# LcsNodes-Dual-Block-Controller-B_02_10.net
KiCad netlist of a schematic drawn in EasyEDA
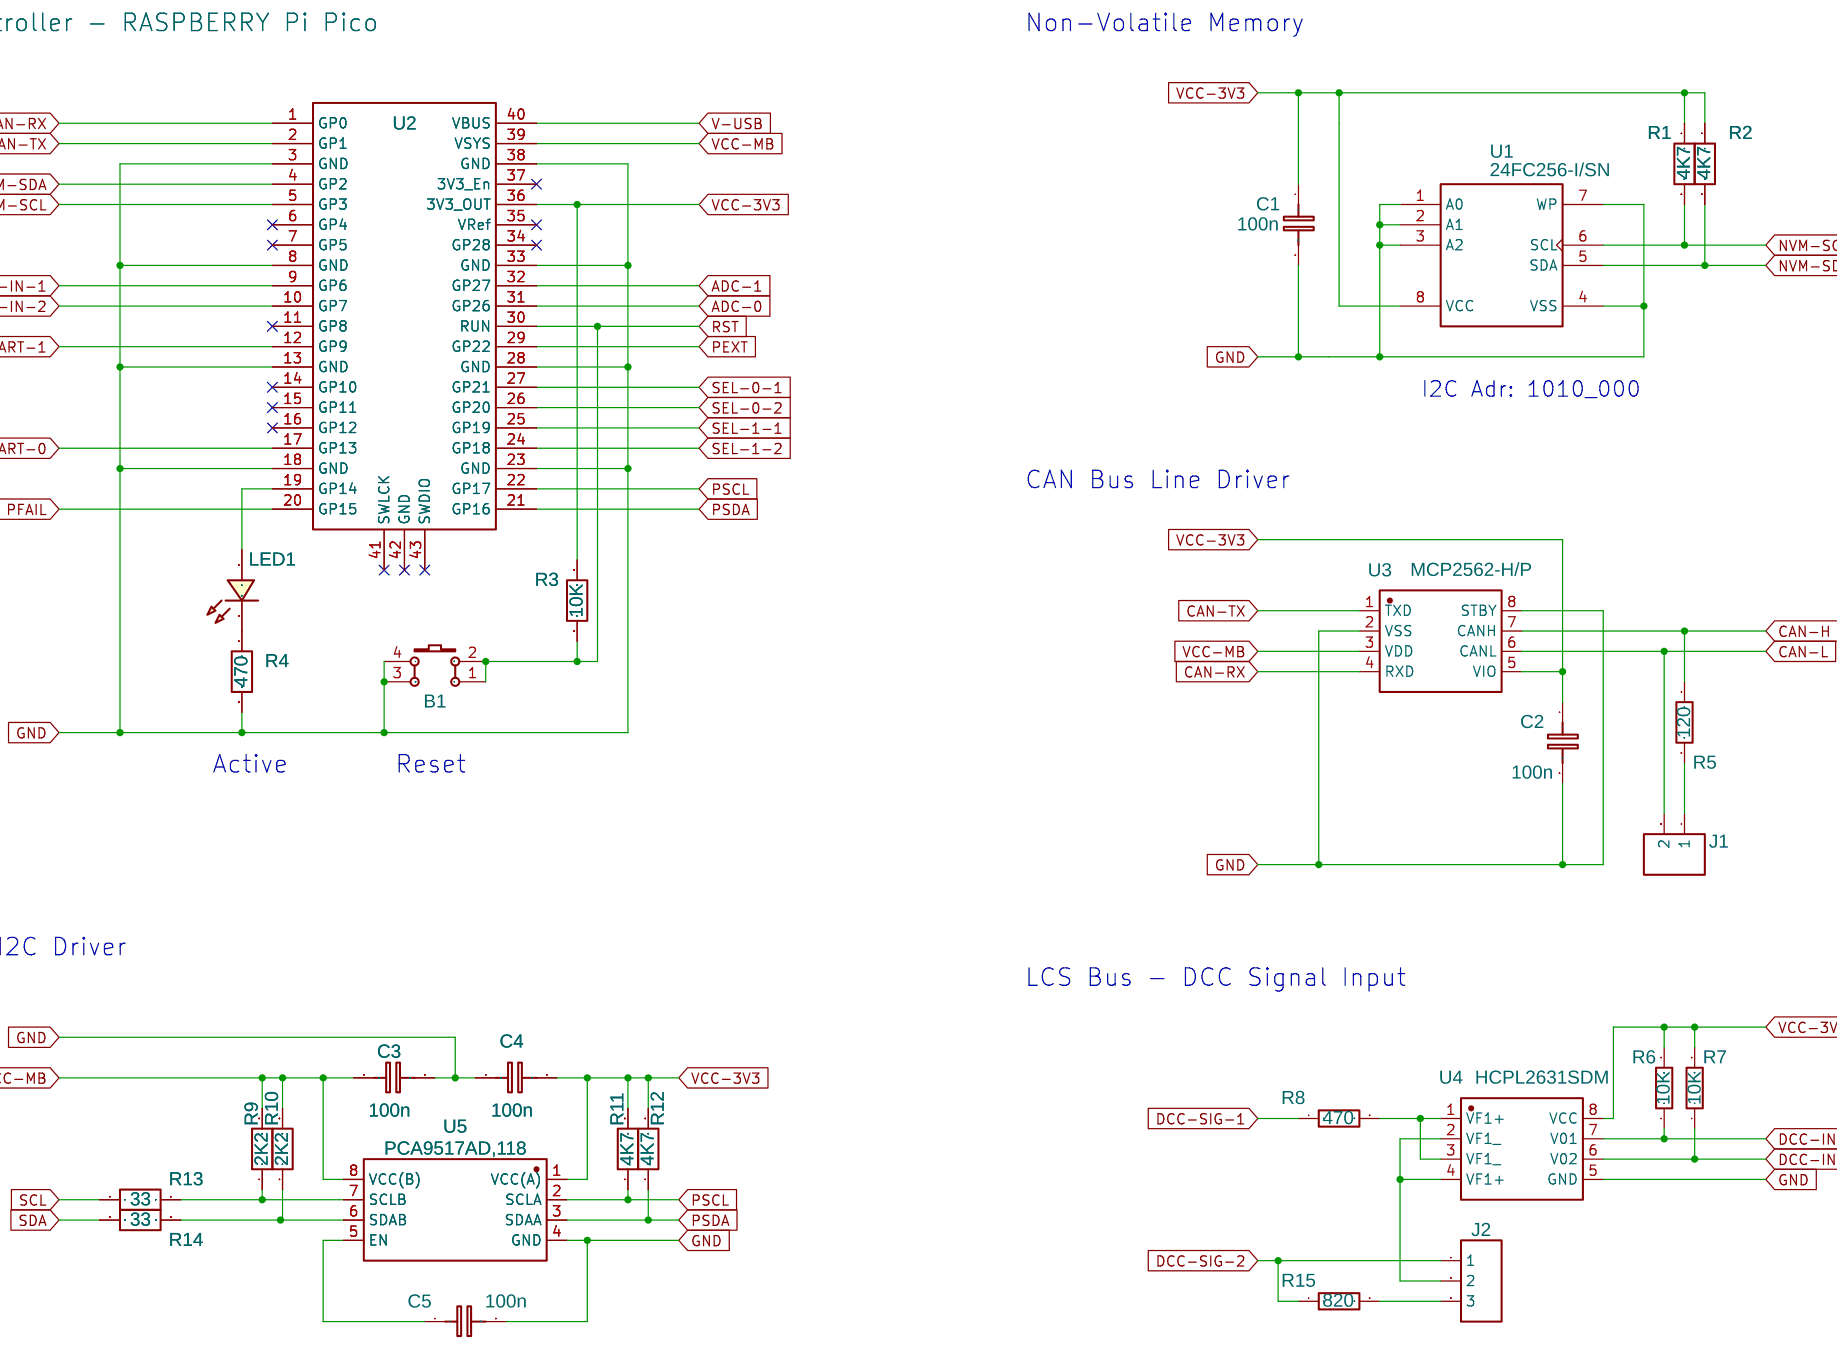
[diagram p0: Main Controller]
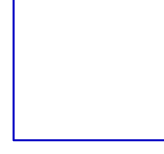
[diagram p1: High Level Schematic]
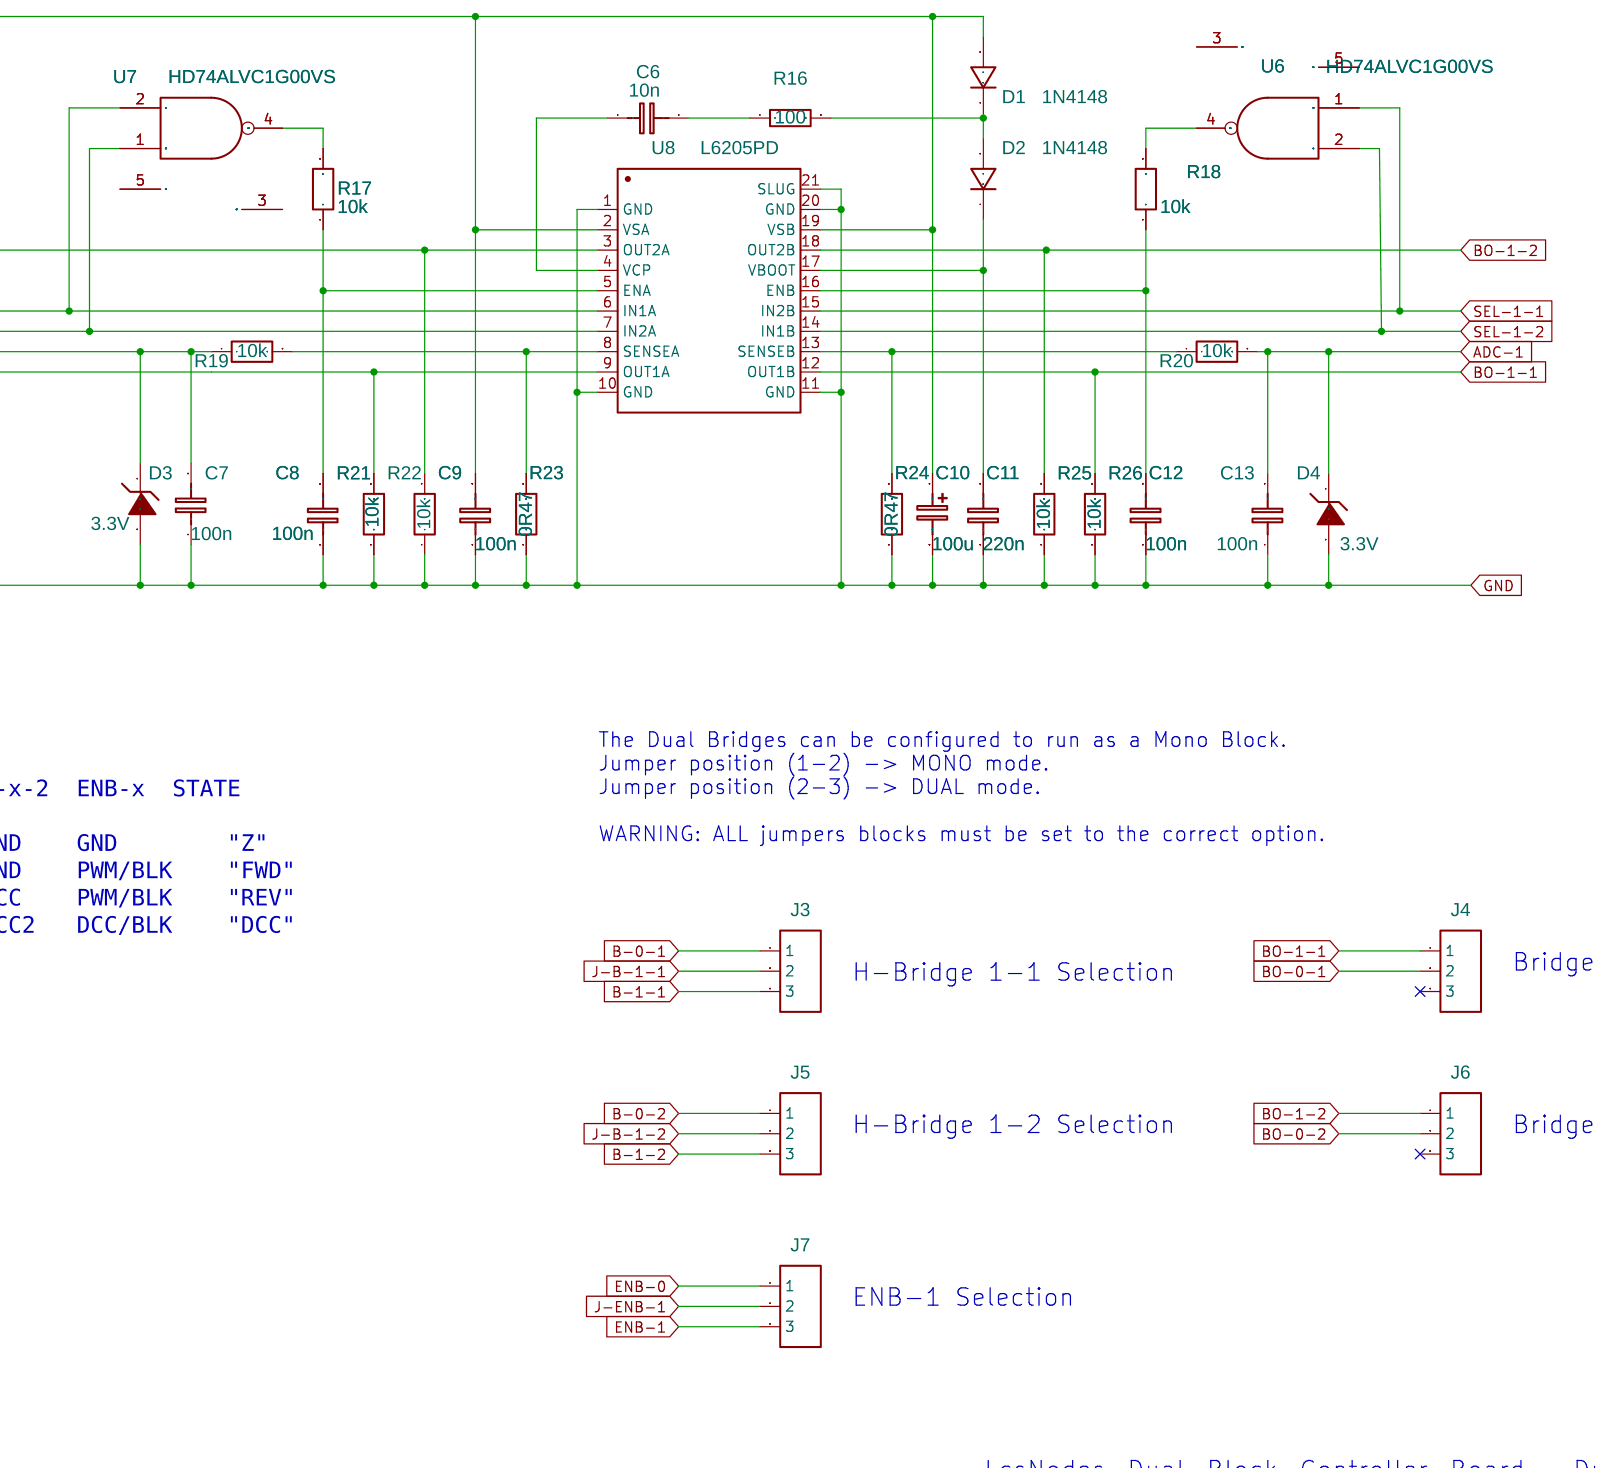
[diagram p2: Dual Power Unit]
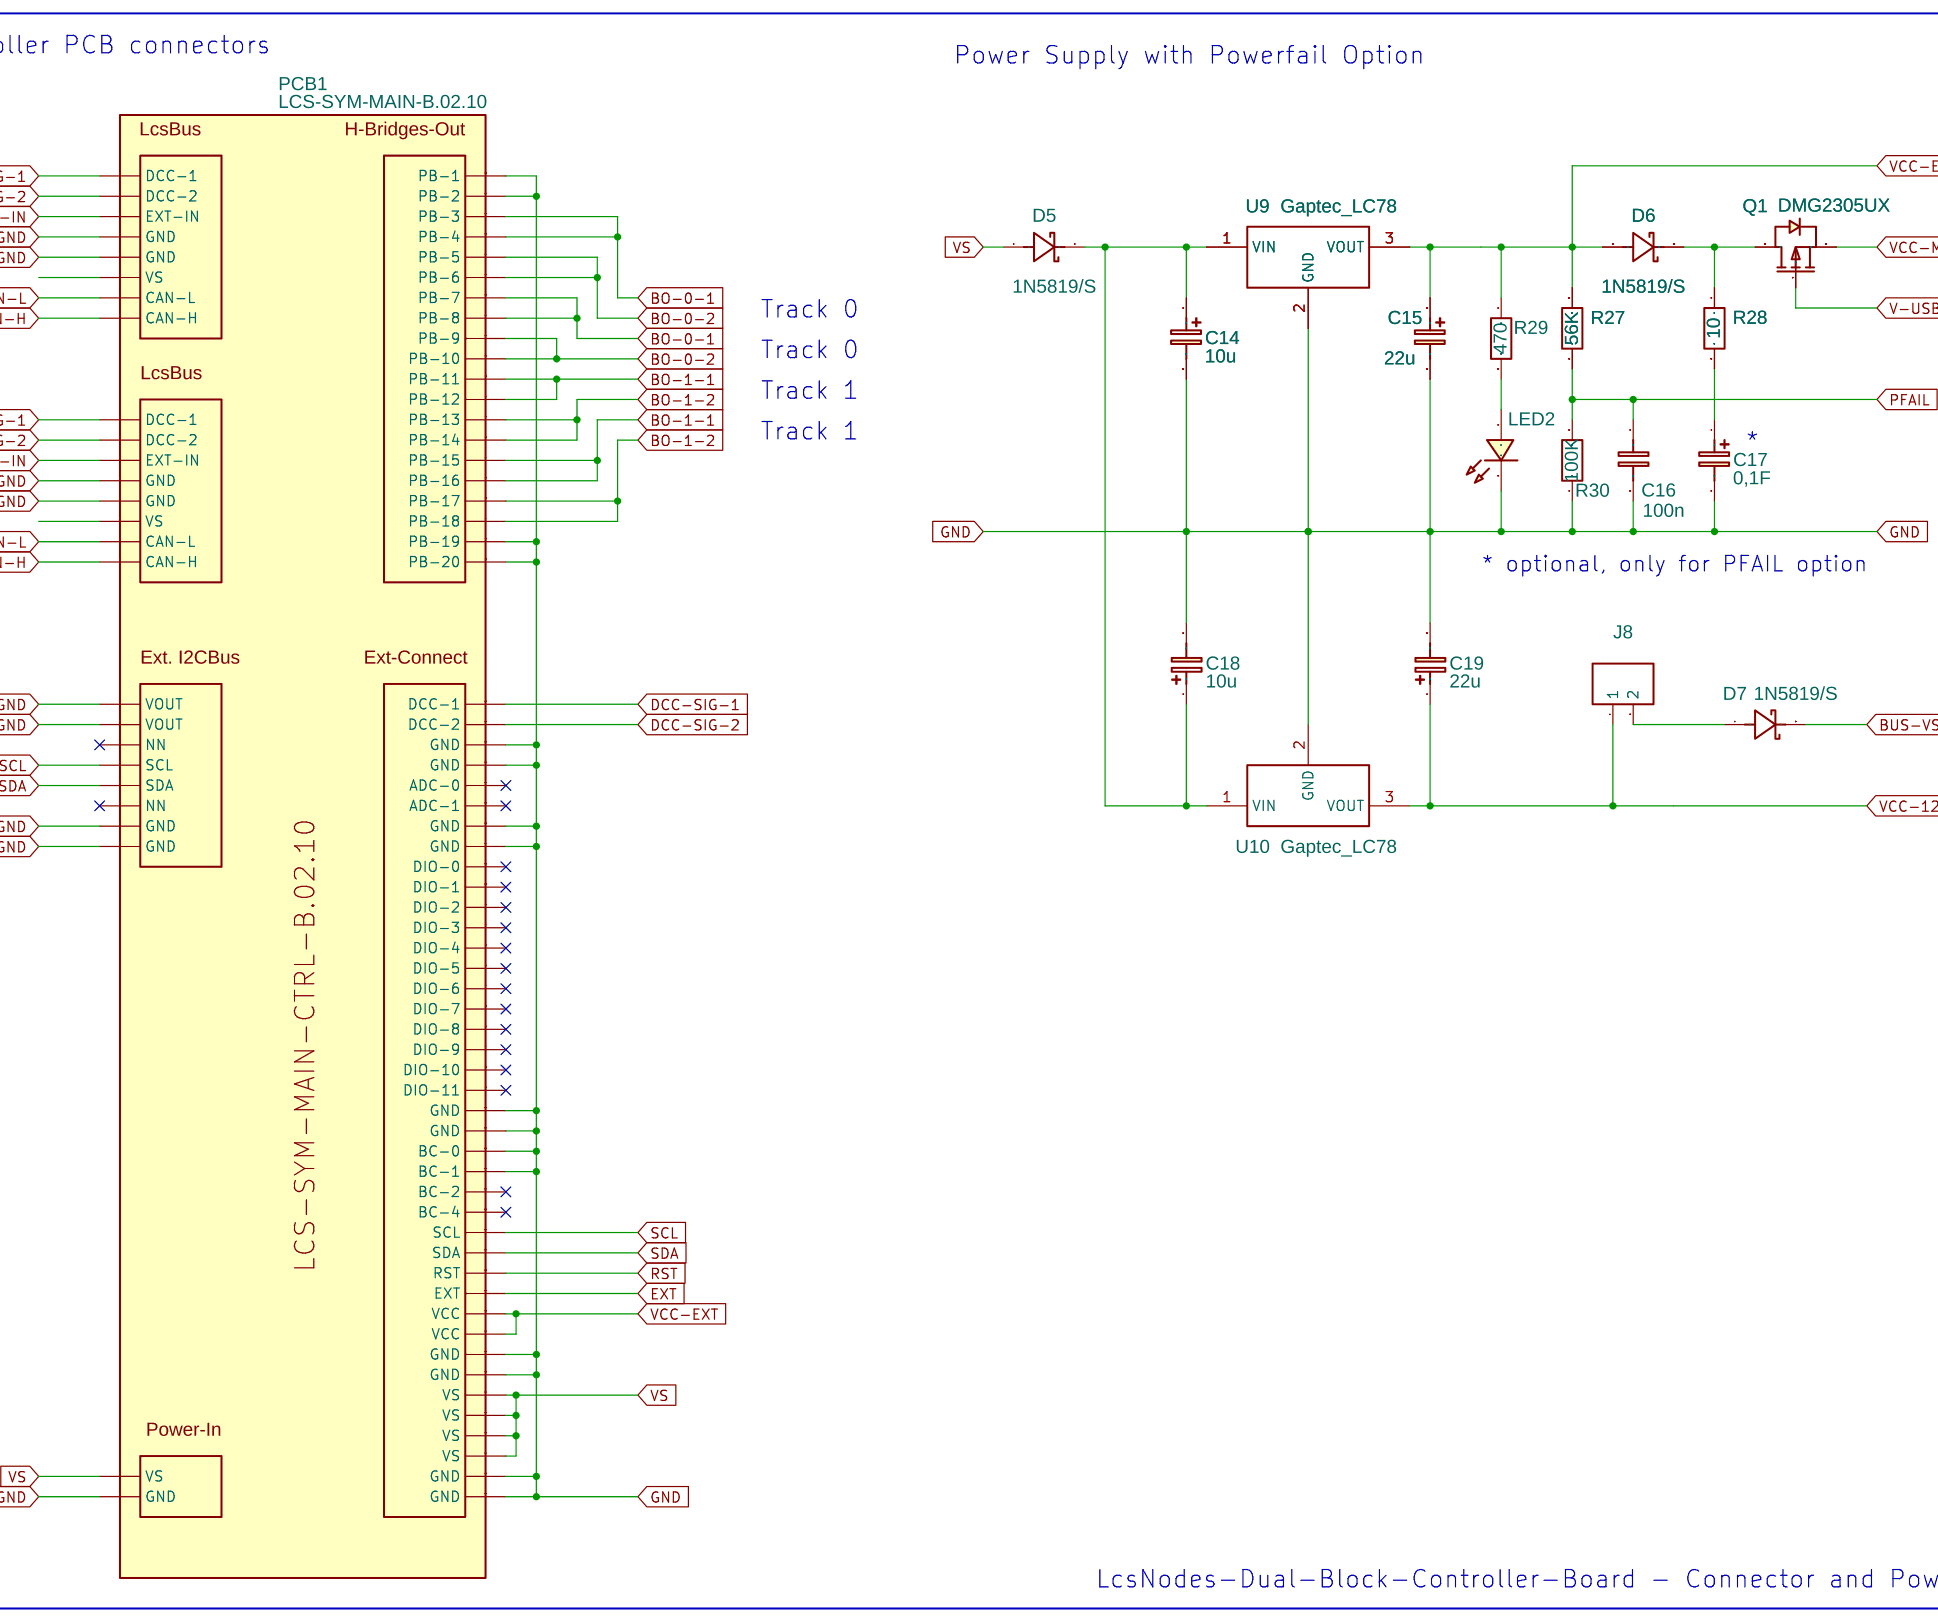
[diagram p3: Power Supply, Connectors]

(export (version "E")
  (design (tool "Eeschema 10.0.6"))
  (components
    (comp (ref "B1")
      (value "Opt")
      (fields (field (name "Manufacturer Part") "K2-1102DP-E4SW-04") (field (name "Manufacturer") "韩国韩荣"))
      (libsource (lib "") (part "K4-6×6_TH"))
    )
    (comp (ref "C1") (value "100n") (libsource (lib "") (part "C_0603_EU_1")))
    (comp (ref "C2") (value "100n") (libsource (lib "") (part "C_0603_EU")))
    (comp (ref "C3") (value "100n") (libsource (lib "") (part "C_RAD-0.2_EU")))
    (comp (ref "C4") (value "100n") (libsource (lib "") (part "C_RAD-0.2_EU")))
    (comp (ref "C5") (value "100n") (libsource (lib "") (part "C_RAD-0.2_EU")))
    (comp (ref "J1") (value "HDR-M-2.54_1x2") (libsource (lib "") (part "HDR-M-2.54_1x2")))
    (comp (ref "J2") (value "HDR-M-2.54_1x3") (libsource (lib "") (part "HDR-M-2.54_1x3")))
    (comp (ref "LED1")
      (value "LED-0805_G")
      (fields (field (name "Manufacturer Part") "NCD0805G1") (field (name "Manufacturer") "国星光电"))
      (libsource (lib "") (part "LED-0805_G"))
    )
    (comp (ref "R1") (value "4K7") (libsource (lib "") (part "R_0805_EU_1")))
    (comp (ref "R2") (value "4K7") (libsource (lib "") (part "R_0805_EU_1")))
    (comp (ref "R3") (value "10K") (libsource (lib "") (part "R_0805_EU")))
    (comp (ref "R4") (value "470") (libsource (lib "") (part "R_0805_EU_1")))
    (comp (ref "R5") (value "120") (libsource (lib "") (part "RESISTOR-AXIAL-0.1")))
    (comp (ref "R6")
      (value "10K")
      (fields (field (name "Manufacturer Part") "SR1206JR-7W4K7L") (field (name "Manufacturer") "YAGEO(国巨)"))
      (libsource (lib "") (part "SR1206JR-7W4K7L"))
    )
    (comp (ref "R7")
      (value "10K")
      (fields (field (name "Manufacturer Part") "SR1206JR-7W4K7L") (field (name "Manufacturer") "YAGEO(国巨)"))
      (libsource (lib "") (part "SR1206JR-7W4K7L"))
    )
    (comp (ref "R8")
      (value "470")
      (fields (field (name "Manufacturer Part") "SR1206JR-7W4K7L") (field (name "Manufacturer") "YAGEO(国巨)"))
      (libsource (lib "") (part "SR1206JR-7W4K7L_1"))
    )
    (comp (ref "R9") (value "2K2") (libsource (lib "") (part "R_0805_EU")))
    (comp (ref "R10") (value "2K2") (libsource (lib "") (part "R_0805_EU")))
    (comp (ref "R11") (value "4K7") (libsource (lib "") (part "R_0805_EU")))
    (comp (ref "R12") (value "4K7") (libsource (lib "") (part "R_0805_EU")))
    (comp (ref "R13") (value "33") (libsource (lib "") (part "R_1206_EU")))
    (comp (ref "R14") (value "33") (libsource (lib "") (part "R_1206_EU")))
    (comp (ref "R15")
      (value "820")
      (fields (field (name "Manufacturer Part") "SR1206JR-7W4K7L") (field (name "Manufacturer") "YAGEO(国巨)"))
      (libsource (lib "") (part "SR1206JR-7W4K7L_1"))
    )
    (comp (ref "U1")
      (value "24FC256-I/SN")
      (fields (field (name "Manufacturer") "MICROCHIP(美国微芯)"))
      (libsource (lib "") (part "24FC256-I/SN"))
    )
    (comp (ref "U2")
      (value "Main Controller - RASPBERRY Pi Pico")
      (libsource (lib "") (part "RASPBERRY Pi Pico Through Holes"))
    )
    (comp (ref "U3")
      (value "MCP2562-H/P")
      (fields (field (name "Manufacturer") "MICROCHIP(美国微芯)"))
      (libsource (lib "") (part "MCP2562-H/P"))
    )
    (comp (ref "U4")
      (value "HCPL2631SDM")
      (fields (field (name "Manufacturer") "onsemi(安森美)"))
      (libsource (lib "") (part "HCPL2631SDM"))
    )
    (comp (ref "U5")
      (value "PCA9517AD,118")
      (fields (field (name "Manufacturer") "NXP(恩智浦)"))
      (libsource (lib "") (part "PCA9517AD,118"))
    )
    (comp (ref "C6") (value "10n") (libsource (lib "") (part "C_0603_EU_2")))
    (comp (ref "C7") (value "100n") (libsource (lib "") (part "C_0603_EU")))
    (comp (ref "C8") (value "100n") (libsource (lib "") (part "C_0603_EU")))
    (comp (ref "C9") (value "100n") (libsource (lib "") (part "C_0603_EU_1")))
    (comp (ref "C10") (value "100u") (libsource (lib "") (part "CE_SMD_D5.0×H5.5_EU")))
    (comp (ref "C11") (value "220n") (libsource (lib "") (part "C_0603_EU_1")))
    (comp (ref "C12") (value "100n") (libsource (lib "") (part "C_0603_EU_1")))
    (comp (ref "C13") (value "100n") (libsource (lib "") (part "C_0603_EU_1")))
    (comp (ref "D1")
      (value "1N4148")
      (fields (field (name "Manufacturer") "SEMTECH"))
      (libsource (lib "") (part "1N4148"))
    )
    (comp (ref "D2")
      (value "1N4148")
      (fields (field (name "Manufacturer") "SEMTECH"))
      (libsource (lib "") (part "1N4148"))
    )
    (comp (ref "D3")
      (value "3.3V")
      (fields (field (name "Manufacturer Part") "Diode Zener") (field (name "Manufacturer") "SEMTECH"))
      (libsource (lib "") (part "Diode Zener"))
    )
    (comp (ref "D4")
      (value "3.3V")
      (fields (field (name "Manufacturer Part") "Diode Zener") (field (name "Manufacturer") "SEMTECH"))
      (libsource (lib "") (part "Diode Zener"))
    )
    (comp (ref "J3") (value "HDR-M-2.54_1x3") (libsource (lib "") (part "HDR-M-2.54_1x3")))
    (comp (ref "J4") (value "HDR-M-2.54_1x3") (libsource (lib "") (part "HDR-M-2.54_1x3")))
    (comp (ref "J5") (value "HDR-M-2.54_1x3") (libsource (lib "") (part "HDR-M-2.54_1x3")))
    (comp (ref "J6") (value "HDR-M-2.54_1x3") (libsource (lib "") (part "HDR-M-2.54_1x3")))
    (comp (ref "J7") (value "HDR-M-2.54_1x3") (libsource (lib "") (part "HDR-M-2.54_1x3")))
    (comp (ref "R16") (value "100") (libsource (lib "") (part "RESISTOR-AXIAL-0.1")))
    (comp (ref "R17") (value "10k") (libsource (lib "") (part "R_AXIAL-0.3_EU")))
    (comp (ref "R18") (value "10k") (libsource (lib "") (part "R_AXIAL-0.3_EU")))
    (comp (ref "R19") (value "10k") (libsource (lib "") (part "R_AXIAL-0.3_EU_1")))
    (comp (ref "R20") (value "10k") (libsource (lib "") (part "R_AXIAL-0.3_EU_1")))
    (comp (ref "R21") (value "10k") (libsource (lib "") (part "R_AXIAL-0.3_EU")))
    (comp (ref "R22") (value "10k") (libsource (lib "") (part "R_AXIAL-0.3_EU")))
    (comp (ref "R23") (value "0R47") (libsource (lib "") (part "R_AXIAL-0.5_EU")))
    (comp (ref "R24") (value "0R47") (libsource (lib "") (part "R_AXIAL-0.5_EU")))
    (comp (ref "R25") (value "10k") (libsource (lib "") (part "R_AXIAL-0.3_EU")))
    (comp (ref "R26") (value "10k") (libsource (lib "") (part "R_AXIAL-0.3_EU")))
    (comp (ref "U6") (value "HD74ALVC1G00VS") (libsource (lib "") (part "HD74ALVC1G00VS_1")))
    (comp (ref "U7") (value "HD74ALVC1G00VS") (libsource (lib "") (part "HD74ALVC1G00VS")))
    (comp (ref "U8")
      (value "L6205PD")
      (fields (field (name "Manufacturer Part") "L6205PD013TR") (field (name "Manufacturer") "ST(意法半导体)"))
      (libsource (lib "") (part "L6205PD"))
    )
    (comp (ref "C14") (value "10u") (libsource (lib "") (part "CE_SMD_D5.0×H5.5_EU")))
    (comp (ref "C15") (value "22u") (libsource (lib "") (part "CE_SMD_D5.0×H5.5_EU")))
    (comp (ref "C16") (value "100n") (libsource (lib "") (part "C_RAD-0.2_EU")))
    (comp (ref "C17") (value "0,1F") (libsource (lib "") (part "C_Tan_SMD_A_EU")))
    (comp (ref "C18") (value "10u") (libsource (lib "") (part "CE_SMD_D5.0×H5.5_EU_1")))
    (comp (ref "C19") (value "22u") (libsource (lib "") (part "CE_SMD_D5.0×H5.5_EU_1")))
    (comp (ref "D5") (value "1N5819/S") (libsource (lib "") (part "1N5819/S")))
    (comp (ref "D6") (value "1N5819/S") (libsource (lib "") (part "1N5819/S")))
    (comp (ref "D7") (value "1N5819/S") (libsource (lib "") (part "1N5819/S")))
    (comp (ref "J8") (value "HDR-M-2.54_1x2") (libsource (lib "") (part "HDR-M-2.54_1x2")))
    (comp (ref "LED2")
      (value "LED-0805_G")
      (fields (field (name "Manufacturer Part") "NCD0805G1") (field (name "Manufacturer") "国星光电"))
      (libsource (lib "") (part "LED-0805_G"))
    )
    (comp (ref "PCB1") (value "LCS-SYM-MAIN-B.02.10") (libsource (lib "") (part "LCS-SYM-MAIN-B.02.10")))
    (comp (ref "Q1")
      (value "DMG2305UX")
      (fields (field (name "Manufacturer") "TECH PUBLIC(台舟)"))
      (libsource (lib "") (part "DMG2305UX"))
    )
    (comp (ref "R27") (value "56K") (libsource (lib "") (part "R_AXIAL-0.3_EU")))
    (comp (ref "R28") (value "10") (libsource (lib "") (part "R_AXIAL-0.3_EU_1")))
    (comp (ref "R29") (value "470") (libsource (lib "") (part "R_0805_EU")))
    (comp (ref "R30") (value "100K") (libsource (lib "") (part "R_AXIAL-0.3_EU")))
    (comp (ref "U9") (value "Gaptec_LC78") (libsource (lib "") (part "Gaptec_LC78_1")))
    (comp (ref "U10") (value "Gaptec_LC78") (libsource (lib "") (part "Gaptec_LC78")))
  )
  (nets
    (net (code "1") (name "ADC-0") (class "Default")
      (node (ref "C7") (pin "2") (pinfunction "2_2") (pintype "unspecified"))
      (node (ref "D3") (pin "1") (pinfunction "C_1") (pintype "unspecified"))
      (node (ref "R19") (pin "1") (pinfunction "1_1") (pintype "unspecified"))
      (node (ref "U2") (pin "31") (pinfunction "GP26_31") (pintype "unspecified"))
    )
    (net (code "2") (name "ADC-1") (class "Default")
      (node (ref "C13") (pin "2") (pinfunction "2_2") (pintype "unspecified"))
      (node (ref "D4") (pin "1") (pinfunction "C_1") (pintype "unspecified"))
      (node (ref "R20") (pin "2") (pinfunction "2_2") (pintype "unspecified"))
      (node (ref "U2") (pin "32") (pinfunction "GP27_32") (pintype "unspecified"))
    )
    (net (code "3") (name "B-0-1") (class "Default")
      (node (ref "J3") (pin "1") (pinfunction "1_1") (pintype "input"))
    )
    (net (code "4") (name "B-0-2") (class "Default")
      (node (ref "J5") (pin "1") (pinfunction "1_1") (pintype "input"))
    )
    (net (code "5") (name "B-1-1") (class "Default")
      (node (ref "J3") (pin "3") (pinfunction "3_3") (pintype "input"))
    )
    (net (code "6") (name "B-1-2") (class "Default")
      (node (ref "J5") (pin "3") (pinfunction "3_3") (pintype "input"))
    )
    (net (code "7") (name "BO-0-1") (class "Default")
      (node (ref "J4") (pin "2") (pinfunction "2_2") (pintype "input"))
      (node (ref "PCB1") (pin "32") (pinfunction "PB-3_32") (pintype "unspecified"))
      (node (ref "PCB1") (pin "33") (pinfunction "PB-4_33") (pintype "unspecified"))
      (node (ref "PCB1") (pin "36") (pinfunction "PB-7_36") (pintype "unspecified"))
      (node (ref "PCB1") (pin "37") (pinfunction "PB-8_37") (pintype "unspecified"))
      (node (ref "R21") (pin "2") (pinfunction "2_2") (pintype "unspecified"))
      (node (ref "U8") (pin "9") (pinfunction "OUT1A_9") (pintype "unspecified"))
    )
    (net (code "8") (name "BO-0-2") (class "Default")
      (node (ref "J6") (pin "2") (pinfunction "2_2") (pintype "input"))
      (node (ref "PCB1") (pin "34") (pinfunction "PB-5_34") (pintype "unspecified"))
      (node (ref "PCB1") (pin "35") (pinfunction "PB-6_35") (pintype "unspecified"))
      (node (ref "PCB1") (pin "38") (pinfunction "PB-9_38") (pintype "unspecified"))
      (node (ref "PCB1") (pin "39") (pinfunction "PB-10_39") (pintype "unspecified"))
      (node (ref "R22") (pin "2") (pinfunction "2_2") (pintype "unspecified"))
      (node (ref "U8") (pin "3") (pinfunction "OUT2A_3") (pintype "unspecified"))
    )
    (net (code "9") (name "BO-1-1") (class "Default")
      (node (ref "J4") (pin "1") (pinfunction "1_1") (pintype "input"))
      (node (ref "PCB1") (pin "40") (pinfunction "PB-11_40") (pintype "unspecified"))
      (node (ref "PCB1") (pin "41") (pinfunction "PB-12_41") (pintype "unspecified"))
      (node (ref "PCB1") (pin "44") (pinfunction "PB-15_44") (pintype "unspecified"))
      (node (ref "PCB1") (pin "45") (pinfunction "PB-16_45") (pintype "unspecified"))
      (node (ref "R26") (pin "2") (pinfunction "2_2") (pintype "unspecified"))
      (node (ref "U8") (pin "12") (pinfunction "OUT1B_12") (pintype "unspecified"))
    )
    (net (code "10") (name "BO-1-2") (class "Default")
      (node (ref "J6") (pin "1") (pinfunction "1_1") (pintype "input"))
      (node (ref "PCB1") (pin "42") (pinfunction "PB-13_42") (pintype "unspecified"))
      (node (ref "PCB1") (pin "43") (pinfunction "PB-14_43") (pintype "unspecified"))
      (node (ref "PCB1") (pin "46") (pinfunction "PB-17_46") (pintype "unspecified"))
      (node (ref "PCB1") (pin "47") (pinfunction "PB-18_47") (pintype "unspecified"))
      (node (ref "R25") (pin "2") (pinfunction "2_2") (pintype "unspecified"))
      (node (ref "U8") (pin "18") (pinfunction "OUT2B_18") (pintype "unspecified"))
    )
    (net (code "11") (name "BUS-VS") (class "Default")
      (node (ref "D7") (pin "2") (pinfunction "K_2") (pintype "unspecified"))
    )
    (net (code "12") (name "CAN-H") (class "Default")
      (node (ref "PCB1") (pin "18") (pinfunction "CAN-H_18") (pintype "unspecified"))
      (node (ref "PCB1") (pin "8") (pinfunction "CAN-H_8") (pintype "unspecified"))
      (node (ref "R5") (pin "1") (pinfunction "1_1") (pintype "input"))
      (node (ref "U3") (pin "7") (pinfunction "CANH_7") (pintype "unspecified"))
    )
    (net (code "13") (name "CAN-L") (class "Default")
      (node (ref "J1") (pin "2") (pinfunction "2_2") (pintype "unspecified"))
      (node (ref "PCB1") (pin "17") (pinfunction "CAN-L_17") (pintype "unspecified"))
      (node (ref "PCB1") (pin "7") (pinfunction "CAN-L_7") (pintype "unspecified"))
      (node (ref "U3") (pin "6") (pinfunction "CANL_6") (pintype "unspecified"))
    )
    (net (code "14") (name "CAN-RX") (class "Default")
      (node (ref "U2") (pin "1") (pinfunction "GP0_1") (pintype "unspecified"))
      (node (ref "U3") (pin "4") (pinfunction "RXD_4") (pintype "unspecified"))
    )
    (net (code "15") (name "CAN-TX") (class "Default")
      (node (ref "U2") (pin "2") (pinfunction "GP1_2") (pintype "unspecified"))
      (node (ref "U3") (pin "1") (pinfunction "TXD_1") (pintype "unspecified"))
    )
    (net (code "16") (name "DCC-IN-1") (class "Default")
      (node (ref "R6") (pin "1") (pinfunction "1_1") (pintype "unspecified"))
      (node (ref "U2") (pin "9") (pinfunction "GP6_9") (pintype "unspecified"))
      (node (ref "U4") (pin "7") (pinfunction "V01_7") (pintype "unspecified"))
    )
    (net (code "17") (name "DCC-IN-2") (class "Default")
      (node (ref "R7") (pin "1") (pinfunction "1_1") (pintype "unspecified"))
      (node (ref "U2") (pin "10") (pinfunction "GP7_10") (pintype "unspecified"))
      (node (ref "U4") (pin "6") (pinfunction "V02_6") (pintype "unspecified"))
    )
    (net (code "18") (name "DCC-SIG-1") (class "Default")
      (node (ref "PCB1") (pin "1") (pinfunction "DCC-1_1") (pintype "unspecified"))
      (node (ref "PCB1") (pin "11") (pinfunction "DCC-1_11") (pintype "unspecified"))
      (node (ref "PCB1") (pin "60") (pinfunction "DCC-1_60") (pintype "unspecified"))
      (node (ref "R8") (pin "1") (pinfunction "1_1") (pintype "unspecified"))
    )
    (net (code "19") (name "DCC-SIG-2") (class "Default")
      (node (ref "J2") (pin "1") (pinfunction "1_1") (pintype "input"))
      (node (ref "PCB1") (pin "12") (pinfunction "DCC-2_12") (pintype "unspecified"))
      (node (ref "PCB1") (pin "2") (pinfunction "DCC-2_2") (pintype "unspecified"))
      (node (ref "PCB1") (pin "61") (pinfunction "DCC-2_61") (pintype "unspecified"))
      (node (ref "R15") (pin "1") (pinfunction "1_1") (pintype "unspecified"))
    )
    (net (code "20") (name "ENB-0") (class "Default")
      (node (ref "J7") (pin "1") (pinfunction "1_1") (pintype "input"))
    )
    (net (code "21") (name "ENB-1") (class "Default")
      (node (ref "J7") (pin "3") (pinfunction "3_3") (pintype "input"))
    )
    (net (code "22") (name "EXT") (class "Default")
      (node (ref "PCB1") (pin "89") (pinfunction "EXT_89") (pintype "unspecified"))
    )
    (net (code "23") (name "EXT-IN") (class "Default")
      (node (ref "PCB1") (pin "13") (pinfunction "EXT-IN_13") (pintype "unspecified"))
      (node (ref "PCB1") (pin "3") (pinfunction "EXT-IN_3") (pintype "unspecified"))
    )
    (net (code "24") (name "GND") (class "Default")
      (node (ref "B1") (pin "3") (pinfunction "3_3") (pintype "unspecified"))
      (node (ref "B1") (pin "4") (pinfunction "4_4") (pintype "unspecified"))
      (node (ref "C1") (pin "2") (pinfunction "2_2") (pintype "unspecified"))
      (node (ref "C10") (pin "2") (pinfunction "2_2") (pintype "unspecified"))
      (node (ref "C11") (pin "1") (pinfunction "1_1") (pintype "unspecified"))
      (node (ref "C12") (pin "1") (pinfunction "1_1") (pintype "unspecified"))
      (node (ref "C13") (pin "1") (pinfunction "1_1") (pintype "unspecified"))
      (node (ref "C14") (pin "2") (pinfunction "2_2") (pintype "unspecified"))
      (node (ref "C15") (pin "2") (pinfunction "2_2") (pintype "unspecified"))
      (node (ref "C16") (pin "2") (pinfunction "2_2") (pintype "unspecified"))
      (node (ref "C17") (pin "2") (pinfunction "2_2") (pintype "unspecified"))
      (node (ref "C18") (pin "2") (pinfunction "2_2") (pintype "unspecified"))
      (node (ref "C19") (pin "2") (pinfunction "2_2") (pintype "unspecified"))
      (node (ref "C2") (pin "2") (pinfunction "2_2") (pintype "unspecified"))
      (node (ref "C3") (pin "2") (pinfunction "2_2") (pintype "unspecified"))
      (node (ref "C4") (pin "1") (pinfunction "1_1") (pintype "unspecified"))
      (node (ref "C5") (pin "2") (pinfunction "2_2") (pintype "unspecified"))
      (node (ref "C7") (pin "1") (pinfunction "1_1") (pintype "unspecified"))
      (node (ref "C8") (pin "1") (pinfunction "1_1") (pintype "unspecified"))
      (node (ref "C9") (pin "1") (pinfunction "1_1") (pintype "unspecified"))
      (node (ref "D3") (pin "2") (pinfunction "A_2") (pintype "unspecified"))
      (node (ref "D4") (pin "2") (pinfunction "A_2") (pintype "unspecified"))
      (node (ref "LED2") (pin "2") (pinfunction "2_2") (pintype "unspecified"))
      (node (ref "PCB1") (pin "101") (pinfunction "GND_101") (pintype "unspecified"))
      (node (ref "PCB1") (pin "14") (pinfunction "GND_14") (pintype "unspecified"))
      (node (ref "PCB1") (pin "15") (pinfunction "GND_15") (pintype "unspecified"))
      (node (ref "PCB1") (pin "21") (pinfunction "VOUT_21") (pintype "unspecified"))
      (node (ref "PCB1") (pin "22") (pinfunction "VOUT_22") (pintype "unspecified"))
      (node (ref "PCB1") (pin "27") (pinfunction "GND_27") (pintype "unspecified"))
      (node (ref "PCB1") (pin "28") (pinfunction "GND_28") (pintype "unspecified"))
      (node (ref "PCB1") (pin "30") (pinfunction "PB-1_30") (pintype "unspecified"))
      (node (ref "PCB1") (pin "31") (pinfunction "PB-2_31") (pintype "unspecified"))
      (node (ref "PCB1") (pin "4") (pinfunction "GND_4") (pintype "unspecified"))
      (node (ref "PCB1") (pin "48") (pinfunction "PB-19_48") (pintype "unspecified"))
      (node (ref "PCB1") (pin "49") (pinfunction "PB-20_49") (pintype "unspecified"))
      (node (ref "PCB1") (pin "5") (pinfunction "GND_5") (pintype "unspecified"))
      (node (ref "PCB1") (pin "62") (pinfunction "GND_62") (pintype "unspecified"))
      (node (ref "PCB1") (pin "63") (pinfunction "GND_63") (pintype "unspecified"))
      (node (ref "PCB1") (pin "66") (pinfunction "GND_66") (pintype "unspecified"))
      (node (ref "PCB1") (pin "67") (pinfunction "GND_67") (pintype "unspecified"))
      (node (ref "PCB1") (pin "80") (pinfunction "GND_80") (pintype "unspecified"))
      (node (ref "PCB1") (pin "81") (pinfunction "GND_81") (pintype "unspecified"))
      (node (ref "PCB1") (pin "82") (pinfunction "BC-0_82") (pintype "unspecified"))
      (node (ref "PCB1") (pin "83") (pinfunction "BC-1_83") (pintype "unspecified"))
      (node (ref "PCB1") (pin "92") (pinfunction "GND_92") (pintype "unspecified"))
      (node (ref "PCB1") (pin "93") (pinfunction "GND_93") (pintype "unspecified"))
      (node (ref "PCB1") (pin "98") (pinfunction "GND_98") (pintype "unspecified"))
      (node (ref "PCB1") (pin "99") (pinfunction "GND_99") (pintype "unspecified"))
      (node (ref "R21") (pin "1") (pinfunction "1_1") (pintype "unspecified"))
      (node (ref "R22") (pin "1") (pinfunction "1_1") (pintype "unspecified"))
      (node (ref "R23") (pin "1") (pinfunction "1_1") (pintype "unspecified"))
      (node (ref "R24") (pin "1") (pinfunction "1_1") (pintype "unspecified"))
      (node (ref "R25") (pin "1") (pinfunction "1_1") (pintype "unspecified"))
      (node (ref "R26") (pin "1") (pinfunction "1_1") (pintype "unspecified"))
      (node (ref "R30") (pin "1") (pinfunction "1_1") (pintype "unspecified"))
      (node (ref "R4") (pin "2") (pinfunction "2_2") (pintype "unspecified"))
      (node (ref "U1") (pin "1") (pinfunction "A0_1") (pintype "unspecified"))
      (node (ref "U1") (pin "2") (pinfunction "A1_2") (pintype "unspecified"))
      (node (ref "U1") (pin "3") (pinfunction "A2_3") (pintype "unspecified"))
      (node (ref "U1") (pin "4") (pinfunction "VSS_4") (pintype "passive"))
      (node (ref "U1") (pin "7") (pinfunction "WP_7") (pintype "unspecified"))
      (node (ref "U10") (pin "2") (pinfunction "GND_2") (pintype "unspecified"))
      (node (ref "U2") (pin "13") (pinfunction "GND_13") (pintype "unspecified"))
      (node (ref "U2") (pin "18") (pinfunction "GND_18") (pintype "unspecified"))
      (node (ref "U2") (pin "23") (pinfunction "GND_23") (pintype "unspecified"))
      (node (ref "U2") (pin "28") (pinfunction "GND_28") (pintype "unspecified"))
      (node (ref "U2") (pin "3") (pinfunction "GND_3") (pintype "unspecified"))
      (node (ref "U2") (pin "33") (pinfunction "GND_33") (pintype "unspecified"))
      (node (ref "U2") (pin "38") (pinfunction "GND_38") (pintype "unspecified"))
      (node (ref "U2") (pin "8") (pinfunction "GND_8") (pintype "unspecified"))
      (node (ref "U3") (pin "2") (pinfunction "VSS_2") (pintype "unspecified"))
      (node (ref "U3") (pin "8") (pinfunction "STBY_8") (pintype "unspecified"))
      (node (ref "U4") (pin "5") (pinfunction "GND_5") (pintype "unspecified"))
      (node (ref "U5") (pin "4") (pinfunction "GND_4") (pintype "unspecified"))
      (node (ref "U8") (pin "1") (pinfunction "GND_1") (pintype "unspecified"))
      (node (ref "U8") (pin "10") (pinfunction "GND_10") (pintype "unspecified"))
      (node (ref "U8") (pin "11") (pinfunction "GND_11") (pintype "unspecified"))
      (node (ref "U8") (pin "20") (pinfunction "GND_20") (pintype "unspecified"))
      (node (ref "U8") (pin "21") (pinfunction "SLUG_21") (pintype "unspecified"))
      (node (ref "U9") (pin "2") (pinfunction "GND_2") (pintype "unspecified"))
    )
    (net (code "25") (name "J-B-1-1") (class "Default")
      (node (ref "J3") (pin "2") (pinfunction "2_2") (pintype "input"))
    )
    (net (code "26") (name "J-B-1-2") (class "Default")
      (node (ref "J5") (pin "2") (pinfunction "2_2") (pintype "input"))
    )
    (net (code "27") (name "J-ENB-1") (class "Default")
      (node (ref "J7") (pin "2") (pinfunction "2_2") (pintype "input"))
    )
    (net (code "28") (name "NVM-SCL") (class "Default")
      (node (ref "R1") (pin "2") (pinfunction "2_2") (pintype "unspecified"))
      (node (ref "U1") (pin "6") (pinfunction "SCL_6") (pintype "unspecified"))
      (node (ref "U2") (pin "5") (pinfunction "GP3_5") (pintype "unspecified"))
    )
    (net (code "29") (name "NVM-SDA") (class "Default")
      (node (ref "R2") (pin "2") (pinfunction "2_2") (pintype "unspecified"))
      (node (ref "U1") (pin "5") (pinfunction "SDA_5") (pintype "bidirectional"))
      (node (ref "U2") (pin "4") (pinfunction "GP2_4") (pintype "unspecified"))
    )
    (net (code "30") (name "Net-(C6-Pad2)") (class "Default")
      (node (ref "C6") (pin "2") (pinfunction "2_2") (pintype "unspecified"))
      (node (ref "R16") (pin "1") (pinfunction "1_1") (pintype "input"))
    )
    (net (code "31") (name "Net-(C17-Pad1)") (class "Default")
      (node (ref "C17") (pin "1") (pinfunction "1_1") (pintype "unspecified"))
      (node (ref "R28") (pin "2") (pinfunction "2_2") (pintype "unspecified"))
    )
    (net (code "32") (name "Net-(D1-2)") (class "Default")
      (node (ref "D1") (pin "1") (pinfunction "2_1") (pintype "unspecified"))
      (node (ref "D2") (pin "2") (pinfunction "1_2") (pintype "unspecified"))
      (node (ref "R16") (pin "2") (pinfunction "2_2") (pintype "input"))
    )
    (net (code "33") (name "Net-(D2-2)") (class "Default")
      (node (ref "C11") (pin "2") (pinfunction "2_2") (pintype "unspecified"))
      (node (ref "D2") (pin "1") (pinfunction "2_1") (pintype "unspecified"))
      (node (ref "U8") (pin "17") (pinfunction "VBOOT_17") (pintype "unspecified"))
    )
    (net (code "34") (name "Net-(D5-K)") (class "Default")
      (node (ref "C14") (pin "1") (pinfunction "1_1") (pintype "unspecified"))
      (node (ref "C18") (pin "1") (pinfunction "1_1") (pintype "unspecified"))
      (node (ref "D5") (pin "2") (pinfunction "K_2") (pintype "unspecified"))
      (node (ref "U10") (pin "1") (pinfunction "VIN_1") (pintype "unspecified"))
      (node (ref "U9") (pin "1") (pinfunction "VIN_1") (pintype "unspecified"))
    )
    (net (code "35") (name "Net-(D6-K)") (class "Default")
      (node (ref "D6") (pin "2") (pinfunction "K_2") (pintype "unspecified"))
      (node (ref "Q1") (pin "3") (pinfunction "D_3") (pintype "unspecified"))
      (node (ref "R28") (pin "1") (pinfunction "1_1") (pintype "unspecified"))
    )
    (net (code "36") (name "Net-(D7-A)") (class "Default")
      (node (ref "D7") (pin "1") (pinfunction "A_1") (pintype "unspecified"))
      (node (ref "J8") (pin "2") (pinfunction "2_2") (pintype "unspecified"))
    )
    (net (code "37") (name "Net-(J1-Pad1)") (class "Default")
      (node (ref "J1") (pin "1") (pinfunction "1_1") (pintype "unspecified"))
      (node (ref "R5") (pin "2") (pinfunction "2_2") (pintype "input"))
    )
    (net (code "38") (name "Net-(J2-Pad2)") (class "Default")
      (node (ref "J2") (pin "2") (pinfunction "2_2") (pintype "input"))
      (node (ref "U4") (pin "2") (pinfunction "VF1__2") (pintype "unspecified"))
      (node (ref "U4") (pin "4") (pinfunction "VF1+_4") (pintype "unspecified"))
    )
    (net (code "39") (name "Net-(J2-Pad3)") (class "Default")
      (node (ref "J2") (pin "3") (pinfunction "3_3") (pintype "input"))
      (node (ref "R15") (pin "2") (pinfunction "2_2") (pintype "unspecified"))
    )
    (net (code "40") (name "Net-(LED1-Pad2)") (class "Default")
      (node (ref "LED1") (pin "2") (pinfunction "2_2") (pintype "unspecified"))
      (node (ref "R4") (pin "1") (pinfunction "1_1") (pintype "unspecified"))
    )
    (net (code "41") (name "Net-(LED2-Pad1)") (class "Default")
      (node (ref "LED2") (pin "1") (pinfunction "1_1") (pintype "unspecified"))
      (node (ref "R29") (pin "2") (pinfunction "2_2") (pintype "unspecified"))
    )
    (net (code "42") (name "Net-(R8-Pad2)") (class "Default")
      (node (ref "R8") (pin "2") (pinfunction "2_2") (pintype "unspecified"))
      (node (ref "U4") (pin "1") (pinfunction "VF1+_1") (pintype "unspecified"))
      (node (ref "U4") (pin "3") (pinfunction "VF1__3") (pintype "unspecified"))
    )
    (net (code "43") (name "Net-(U2-GP14)") (class "Default")
      (node (ref "LED1") (pin "1") (pinfunction "1_1") (pintype "unspecified"))
      (node (ref "U2") (pin "19") (pinfunction "GP14_19") (pintype "unspecified"))
    )
    (net (code "44") (name "Net-(U5-EN)") (class "Default")
      (node (ref "C5") (pin "1") (pinfunction "1_1") (pintype "unspecified"))
      (node (ref "U5") (pin "5") (pinfunction "EN_5") (pintype "unspecified"))
    )
    (net (code "45") (name "Net-(U5-SCLB)") (class "Default")
      (node (ref "R13") (pin "2") (pinfunction "2_2") (pintype "unspecified"))
      (node (ref "R9") (pin "1") (pinfunction "1_1") (pintype "unspecified"))
      (node (ref "U5") (pin "7") (pinfunction "SCLB_7") (pintype "unspecified"))
    )
    (net (code "46") (name "Net-(U5-SDAB)") (class "Default")
      (node (ref "R10") (pin "1") (pinfunction "1_1") (pintype "unspecified"))
      (node (ref "R14") (pin "2") (pinfunction "2_2") (pintype "unspecified"))
      (node (ref "U5") (pin "6") (pinfunction "SDAB_6") (pintype "unspecified"))
    )
    (net (code "47") (name "Net-(U6-OUT_Y)") (class "Default")
      (node (ref "R18") (pin "2") (pinfunction "2_2") (pintype "unspecified"))
      (node (ref "U6") (pin "4") (pinfunction "OUT_Y_4") (pintype "output"))
    )
    (net (code "48") (name "Net-(U7-OUT_Y)") (class "Default")
      (node (ref "R17") (pin "2") (pinfunction "2_2") (pintype "unspecified"))
      (node (ref "U7") (pin "4") (pinfunction "OUT_Y_4") (pintype "output"))
    )
    (net (code "49") (name "Net-(U8-ENA)") (class "Default")
      (node (ref "C8") (pin "2") (pinfunction "2_2") (pintype "unspecified"))
      (node (ref "R17") (pin "1") (pinfunction "1_1") (pintype "unspecified"))
      (node (ref "U8") (pin "5") (pinfunction "ENA_5") (pintype "unspecified"))
    )
    (net (code "50") (name "Net-(U8-ENB)") (class "Default")
      (node (ref "C12") (pin "2") (pinfunction "2_2") (pintype "unspecified"))
      (node (ref "R18") (pin "1") (pinfunction "1_1") (pintype "unspecified"))
      (node (ref "U8") (pin "16") (pinfunction "ENB_16") (pintype "unspecified"))
    )
    (net (code "51") (name "Net-(U8-SENSEA)") (class "Default")
      (node (ref "R19") (pin "2") (pinfunction "2_2") (pintype "unspecified"))
      (node (ref "R23") (pin "2") (pinfunction "2_2") (pintype "unspecified"))
      (node (ref "U8") (pin "8") (pinfunction "SENSEA_8") (pintype "unspecified"))
    )
    (net (code "52") (name "Net-(U8-SENSEB)") (class "Default")
      (node (ref "R20") (pin "1") (pinfunction "1_1") (pintype "unspecified"))
      (node (ref "R24") (pin "2") (pinfunction "2_2") (pintype "unspecified"))
      (node (ref "U8") (pin "13") (pinfunction "SENSEB_13") (pintype "unspecified"))
    )
    (net (code "53") (name "Net-(U8-VCP)") (class "Default")
      (node (ref "C6") (pin "1") (pinfunction "1_1") (pintype "unspecified"))
      (node (ref "U8") (pin "4") (pinfunction "VCP_4") (pintype "unspecified"))
    )
    (net (code "54") (name "PEXT") (class "Default")
      (node (ref "U2") (pin "29") (pinfunction "GP22_29") (pintype "unspecified"))
    )
    (net (code "55") (name "PFAIL") (class "Default")
      (node (ref "C16") (pin "1") (pinfunction "1_1") (pintype "unspecified"))
      (node (ref "R27") (pin "1") (pinfunction "1_1") (pintype "unspecified"))
      (node (ref "R30") (pin "2") (pinfunction "2_2") (pintype "unspecified"))
      (node (ref "U2") (pin "20") (pinfunction "GP15_20") (pintype "unspecified"))
    )
    (net (code "56") (name "PSCL") (class "Default")
      (node (ref "R11") (pin "1") (pinfunction "1_1") (pintype "unspecified"))
      (node (ref "U2") (pin "22") (pinfunction "GP17_22") (pintype "unspecified"))
      (node (ref "U5") (pin "2") (pinfunction "SCLA_2") (pintype "unspecified"))
    )
    (net (code "57") (name "PSDA") (class "Default")
      (node (ref "R12") (pin "1") (pinfunction "1_1") (pintype "unspecified"))
      (node (ref "U2") (pin "21") (pinfunction "GP16_21") (pintype "unspecified"))
      (node (ref "U5") (pin "3") (pinfunction "SDAA_3") (pintype "unspecified"))
    )
    (net (code "58") (name "RST") (class "Default")
      (node (ref "B1") (pin "1") (pinfunction "1_1") (pintype "unspecified"))
      (node (ref "B1") (pin "2") (pinfunction "2_2") (pintype "unspecified"))
      (node (ref "PCB1") (pin "88") (pinfunction "RST_88") (pintype "unspecified"))
      (node (ref "R3") (pin "1") (pinfunction "1_1") (pintype "unspecified"))
      (node (ref "U2") (pin "30") (pinfunction "RUN_30") (pintype "unspecified"))
    )
    (net (code "59") (name "SCL") (class "Default")
      (node (ref "PCB1") (pin "24") (pinfunction "SCL_24") (pintype "unspecified"))
      (node (ref "PCB1") (pin "86") (pinfunction "SCL_86") (pintype "unspecified"))
      (node (ref "R13") (pin "1") (pinfunction "1_1") (pintype "unspecified"))
    )
    (net (code "60") (name "SDA") (class "Default")
      (node (ref "PCB1") (pin "25") (pinfunction "SDA_25") (pintype "unspecified"))
      (node (ref "PCB1") (pin "87") (pinfunction "SDA_87") (pintype "unspecified"))
      (node (ref "R14") (pin "1") (pinfunction "1_1") (pintype "unspecified"))
    )
    (net (code "61") (name "SEL-0-1") (class "Default")
      (node (ref "U2") (pin "27") (pinfunction "GP21_27") (pintype "unspecified"))
      (node (ref "U7") (pin "2") (pinfunction "IN_A_2") (pintype "unspecified"))
      (node (ref "U8") (pin "6") (pinfunction "IN1A_6") (pintype "unspecified"))
    )
    (net (code "62") (name "SEL-0-2") (class "Default")
      (node (ref "U2") (pin "26") (pinfunction "GP20_26") (pintype "unspecified"))
      (node (ref "U7") (pin "1") (pinfunction "IN_B_1") (pintype "unspecified"))
      (node (ref "U8") (pin "7") (pinfunction "IN2A_7") (pintype "unspecified"))
    )
    (net (code "63") (name "SEL-1-1") (class "Default")
      (node (ref "U2") (pin "25") (pinfunction "GP19_25") (pintype "unspecified"))
      (node (ref "U6") (pin "1") (pinfunction "IN_B_1") (pintype "unspecified"))
      (node (ref "U8") (pin "15") (pinfunction "IN2B_15") (pintype "unspecified"))
    )
    (net (code "64") (name "SEL-1-2") (class "Default")
      (node (ref "U2") (pin "24") (pinfunction "GP18_24") (pintype "unspecified"))
      (node (ref "U6") (pin "2") (pinfunction "IN_A_2") (pintype "unspecified"))
      (node (ref "U8") (pin "14") (pinfunction "IN1B_14") (pintype "unspecified"))
    )
    (net (code "65") (name "UART-0") (class "Default")
      (node (ref "U2") (pin "17") (pinfunction "GP13_17") (pintype "unspecified"))
    )
    (net (code "66") (name "UART-1") (class "Default")
      (node (ref "U2") (pin "12") (pinfunction "GP9_12") (pintype "unspecified"))
    )
    (net (code "67") (name "V-USB") (class "Default")
      (node (ref "Q1") (pin "1") (pinfunction "G_1") (pintype "unspecified"))
      (node (ref "U2") (pin "40") (pinfunction "VBUS_40") (pintype "unspecified"))
    )
    (net (code "68") (name "VCC-3V3") (class "Default")
      (node (ref "C1") (pin "1") (pinfunction "1_1") (pintype "unspecified"))
      (node (ref "C2") (pin "1") (pinfunction "1_1") (pintype "unspecified"))
      (node (ref "C4") (pin "2") (pinfunction "2_2") (pintype "unspecified"))
      (node (ref "R1") (pin "1") (pinfunction "1_1") (pintype "unspecified"))
      (node (ref "R11") (pin "2") (pinfunction "2_2") (pintype "unspecified"))
      (node (ref "R12") (pin "2") (pinfunction "2_2") (pintype "unspecified"))
      (node (ref "R2") (pin "1") (pinfunction "1_1") (pintype "unspecified"))
      (node (ref "R3") (pin "2") (pinfunction "2_2") (pintype "unspecified"))
      (node (ref "R6") (pin "2") (pinfunction "2_2") (pintype "unspecified"))
      (node (ref "R7") (pin "2") (pinfunction "2_2") (pintype "unspecified"))
      (node (ref "U1") (pin "8") (pinfunction "VCC_8") (pintype "passive"))
      (node (ref "U2") (pin "36") (pinfunction "3V3_OUT_36") (pintype "unspecified"))
      (node (ref "U3") (pin "5") (pinfunction "VIO_5") (pintype "unspecified"))
      (node (ref "U4") (pin "8") (pinfunction "VCC_8") (pintype "unspecified"))
      (node (ref "U5") (pin "1") (pinfunction "VCC(A)_1") (pintype "unspecified"))
    )
    (net (code "69") (name "VCC-12V") (class "Default")
      (node (ref "C19") (pin "1") (pinfunction "1_1") (pintype "unspecified"))
      (node (ref "J8") (pin "1") (pinfunction "1_1") (pintype "unspecified"))
      (node (ref "U10") (pin "3") (pinfunction "VOUT_3") (pintype "unspecified"))
    )
    (net (code "70") (name "VCC-EXT") (class "Default")
      (node (ref "C15") (pin "1") (pinfunction "1_1") (pintype "unspecified"))
      (node (ref "D6") (pin "1") (pinfunction "A_1") (pintype "unspecified"))
      (node (ref "PCB1") (pin "90") (pinfunction "VCC_90") (pintype "unspecified"))
      (node (ref "PCB1") (pin "91") (pinfunction "VCC_91") (pintype "unspecified"))
      (node (ref "R27") (pin "2") (pinfunction "2_2") (pintype "unspecified"))
      (node (ref "R29") (pin "1") (pinfunction "1_1") (pintype "unspecified"))
      (node (ref "U9") (pin "3") (pinfunction "VOUT_3") (pintype "unspecified"))
    )
    (net (code "71") (name "VCC-MB") (class "Default")
      (node (ref "C3") (pin "1") (pinfunction "1_1") (pintype "unspecified"))
      (node (ref "Q1") (pin "2") (pinfunction "S_2") (pintype "unspecified"))
      (node (ref "R10") (pin "2") (pinfunction "2_2") (pintype "unspecified"))
      (node (ref "R9") (pin "2") (pinfunction "2_2") (pintype "unspecified"))
      (node (ref "U2") (pin "39") (pinfunction "VSYS_39") (pintype "unspecified"))
      (node (ref "U3") (pin "3") (pinfunction "VDD_3") (pintype "unspecified"))
      (node (ref "U5") (pin "8") (pinfunction "VCC(B)_8") (pintype "unspecified"))
    )
    (net (code "72") (name "VS") (class "Default")
      (node (ref "C10") (pin "1") (pinfunction "1_1") (pintype "unspecified"))
      (node (ref "C9") (pin "2") (pinfunction "2_2") (pintype "unspecified"))
      (node (ref "D1") (pin "2") (pinfunction "1_2") (pintype "unspecified"))
      (node (ref "D5") (pin "1") (pinfunction "A_1") (pintype "unspecified"))
      (node (ref "PCB1") (pin "100") (pinfunction "VS_100") (pintype "unspecified"))
      (node (ref "PCB1") (pin "94") (pinfunction "VS_94") (pintype "unspecified"))
      (node (ref "PCB1") (pin "95") (pinfunction "VS_95") (pintype "unspecified"))
      (node (ref "PCB1") (pin "96") (pinfunction "VS_96") (pintype "unspecified"))
      (node (ref "PCB1") (pin "97") (pinfunction "VS_97") (pintype "unspecified"))
      (node (ref "U8") (pin "19") (pinfunction "VSB_19") (pintype "unspecified"))
      (node (ref "U8") (pin "2") (pinfunction "VSA_2") (pintype "unspecified"))
    )
    (net (code "73") (name "unconnected-(J4-Pad3)") (class "Default")
      (node (ref "J4") (pin "3") (pinfunction "3_3") (pintype "input+no_connect"))
    )
    (net (code "74") (name "unconnected-(J6-Pad3)") (class "Default")
      (node (ref "J6") (pin "3") (pinfunction "3_3") (pintype "input+no_connect"))
    )
    (net (code "75") (name "unconnected-(PCB1-ADC-0-Pad64)") (class "Default")
      (node (ref "PCB1") (pin "64") (pinfunction "ADC-0_64") (pintype "unspecified+no_connect"))
    )
    (net (code "76") (name "unconnected-(PCB1-ADC-1-Pad65)") (class "Default")
      (node (ref "PCB1") (pin "65") (pinfunction "ADC-1_65") (pintype "unspecified+no_connect"))
    )
    (net (code "77") (name "unconnected-(PCB1-BC-2-Pad84)") (class "Default")
      (node (ref "PCB1") (pin "84") (pinfunction "BC-2_84") (pintype "unspecified+no_connect"))
    )
    (net (code "78") (name "unconnected-(PCB1-BC-4-Pad85)") (class "Default")
      (node (ref "PCB1") (pin "85") (pinfunction "BC-4_85") (pintype "unspecified+no_connect"))
    )
    (net (code "79") (name "unconnected-(PCB1-DIO-0-Pad68)") (class "Default")
      (node (ref "PCB1") (pin "68") (pinfunction "DIO-0_68") (pintype "unspecified+no_connect"))
    )
    (net (code "80") (name "unconnected-(PCB1-DIO-1-Pad69)") (class "Default")
      (node (ref "PCB1") (pin "69") (pinfunction "DIO-1_69") (pintype "unspecified+no_connect"))
    )
    (net (code "81") (name "unconnected-(PCB1-DIO-2-Pad70)") (class "Default")
      (node (ref "PCB1") (pin "70") (pinfunction "DIO-2_70") (pintype "unspecified+no_connect"))
    )
    (net (code "82") (name "unconnected-(PCB1-DIO-3-Pad71)") (class "Default")
      (node (ref "PCB1") (pin "71") (pinfunction "DIO-3_71") (pintype "unspecified+no_connect"))
    )
    (net (code "83") (name "unconnected-(PCB1-DIO-4-Pad72)") (class "Default")
      (node (ref "PCB1") (pin "72") (pinfunction "DIO-4_72") (pintype "unspecified+no_connect"))
    )
    (net (code "84") (name "unconnected-(PCB1-DIO-5-Pad73)") (class "Default")
      (node (ref "PCB1") (pin "73") (pinfunction "DIO-5_73") (pintype "unspecified+no_connect"))
    )
    (net (code "85") (name "unconnected-(PCB1-DIO-6-Pad74)") (class "Default")
      (node (ref "PCB1") (pin "74") (pinfunction "DIO-6_74") (pintype "unspecified+no_connect"))
    )
    (net (code "86") (name "unconnected-(PCB1-DIO-7-Pad75)") (class "Default")
      (node (ref "PCB1") (pin "75") (pinfunction "DIO-7_75") (pintype "unspecified+no_connect"))
    )
    (net (code "87") (name "unconnected-(PCB1-DIO-8-Pad76)") (class "Default")
      (node (ref "PCB1") (pin "76") (pinfunction "DIO-8_76") (pintype "unspecified+no_connect"))
    )
    (net (code "88") (name "unconnected-(PCB1-DIO-9-Pad77)") (class "Default")
      (node (ref "PCB1") (pin "77") (pinfunction "DIO-9_77") (pintype "unspecified+no_connect"))
    )
    (net (code "89") (name "unconnected-(PCB1-DIO-10-Pad78)") (class "Default")
      (node (ref "PCB1") (pin "78") (pinfunction "DIO-10_78") (pintype "unspecified+no_connect"))
    )
    (net (code "90") (name "unconnected-(PCB1-DIO-11-Pad79)") (class "Default")
      (node (ref "PCB1") (pin "79") (pinfunction "DIO-11_79") (pintype "unspecified+no_connect"))
    )
    (net (code "91") (name "unconnected-(PCB1-NN-Pad23)") (class "Default")
      (node (ref "PCB1") (pin "23") (pinfunction "NN_23") (pintype "unspecified+no_connect"))
    )
    (net (code "92") (name "unconnected-(PCB1-NN-Pad26)") (class "Default")
      (node (ref "PCB1") (pin "26") (pinfunction "NN_26") (pintype "unspecified+no_connect"))
    )
    (net (code "93") (name "unconnected-(PCB1-VS-Pad6)") (class "Default")
      (node (ref "PCB1") (pin "6") (pinfunction "VS_6") (pintype "unspecified"))
    )
    (net (code "94") (name "unconnected-(PCB1-VS-Pad16)") (class "Default")
      (node (ref "PCB1") (pin "16") (pinfunction "VS_16") (pintype "unspecified"))
    )
    (net (code "95") (name "unconnected-(U2-3V3_En-Pad37)") (class "Default")
      (node (ref "U2") (pin "37") (pinfunction "3V3_En_37") (pintype "unspecified+no_connect"))
    )
    (net (code "96") (name "unconnected-(U2-GND-Pad42)") (class "Default")
      (node (ref "U2") (pin "42") (pinfunction "GND_42") (pintype "unspecified+no_connect"))
    )
    (net (code "97") (name "unconnected-(U2-GP4-Pad6)") (class "Default")
      (node (ref "U2") (pin "6") (pinfunction "GP4_6") (pintype "unspecified+no_connect"))
    )
    (net (code "98") (name "unconnected-(U2-GP5-Pad7)") (class "Default")
      (node (ref "U2") (pin "7") (pinfunction "GP5_7") (pintype "unspecified+no_connect"))
    )
    (net (code "99") (name "unconnected-(U2-GP8-Pad11)") (class "Default")
      (node (ref "U2") (pin "11") (pinfunction "GP8_11") (pintype "unspecified+no_connect"))
    )
    (net (code "100") (name "unconnected-(U2-GP10-Pad14)") (class "Default")
      (node (ref "U2") (pin "14") (pinfunction "GP10_14") (pintype "unspecified+no_connect"))
    )
    (net (code "101") (name "unconnected-(U2-GP11-Pad15)") (class "Default")
      (node (ref "U2") (pin "15") (pinfunction "GP11_15") (pintype "unspecified+no_connect"))
    )
    (net (code "102") (name "unconnected-(U2-GP12-Pad16)") (class "Default")
      (node (ref "U2") (pin "16") (pinfunction "GP12_16") (pintype "unspecified+no_connect"))
    )
    (net (code "103") (name "unconnected-(U2-GP28-Pad34)") (class "Default")
      (node (ref "U2") (pin "34") (pinfunction "GP28_34") (pintype "unspecified+no_connect"))
    )
    (net (code "104") (name "unconnected-(U2-SWDIO-Pad43)") (class "Default")
      (node (ref "U2") (pin "43") (pinfunction "SWDIO_43") (pintype "unspecified+no_connect"))
    )
    (net (code "105") (name "unconnected-(U2-SWLCK-Pad41)") (class "Default")
      (node (ref "U2") (pin "41") (pinfunction "SWLCK_41") (pintype "unspecified+no_connect"))
    )
    (net (code "106") (name "unconnected-(U2-VRef-Pad35)") (class "Default")
      (node (ref "U2") (pin "35") (pinfunction "VRef_35") (pintype "unspecified+no_connect"))
    )
    (net (code "107") (name "unconnected-(U6-GND-Pad3)") (class "Default")
      (node (ref "U6") (pin "3") (pinfunction "GND_3") (pintype "passive"))
    )
    (net (code "108") (name "unconnected-(U6-VCC-Pad5)") (class "Default")
      (node (ref "U6") (pin "5") (pinfunction "VCC_5") (pintype "passive"))
    )
    (net (code "109") (name "unconnected-(U7-GND-Pad3)") (class "Default")
      (node (ref "U7") (pin "3") (pinfunction "GND_3") (pintype "passive"))
    )
    (net (code "110") (name "unconnected-(U7-VCC-Pad5)") (class "Default")
      (node (ref "U7") (pin "5") (pinfunction "VCC_5") (pintype "passive"))
    )
  )
)
